# LEDboard.net
KiCad netlist of a schematic drawn in EAGLE
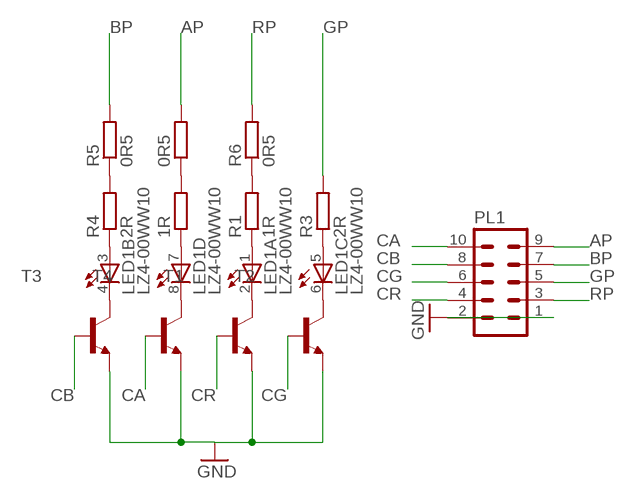
[diagram p0: schematic, sheet 1]

(export (version "E")
  (design (tool "Eeschema 10.0.6"))
  (components
    (comp (ref "0R5")
      (value "R-EU_R0805")
      (footprint "eagle-import:R0805")
      (libsource (lib "eagle-import") (part "R-EU_R0805"))
    )
    (comp (ref "1R")
      (value "R-EU_R1210")
      (footprint "eagle-import:R1210")
      (libsource (lib "eagle-import") (part "R-EU_R1210"))
    )
    (comp (ref "LED1")
      (value "LZ4-00WW10")
      (footprint "eagle-import:LZ4-00WW10")
      (libsource (lib "eagle-import") (part "LZ4-00WW10"))
    )
    (comp (ref "PL1")
      (value "10V")
      (footprint "eagle-import:10V")
      (libsource (lib "eagle-import") (part "10V"))
    )
    (comp (ref "R1")
      (value "1R")
      (footprint "eagle-import:R1210")
      (libsource (lib "eagle-import") (part "R-EU_R1210"))
    )
    (comp (ref "R3")
      (value "2R")
      (footprint "eagle-import:R2512")
      (libsource (lib "eagle-import") (part "R-EU_R2512"))
    )
    (comp (ref "R4")
      (value "2R")
      (footprint "eagle-import:R2512")
      (libsource (lib "eagle-import") (part "R-EU_R2512"))
    )
    (comp (ref "R5")
      (value "0R5")
      (footprint "eagle-import:R0805")
      (libsource (lib "eagle-import") (part "R-EU_R0805"))
    )
    (comp (ref "R6")
      (value "0R5")
      (footprint "eagle-import:R0805")
      (libsource (lib "eagle-import") (part "R-EU_R0805"))
    )
    (comp (ref "T1")
      (value "PZT2222A-NPN-SOT223")
      (footprint "eagle-import:SOT223")
      (libsource (lib "eagle-import") (part "-NPN-SOT223PZT2222A"))
    )
    (comp (ref "T2")
      (value "PZT2222A-NPN-SOT223")
      (footprint "eagle-import:SOT223")
      (libsource (lib "eagle-import") (part "-NPN-SOT223PZT2222A"))
    )
    (comp (ref "T3")
      (value "PZT2222A-NPN-SOT223")
      (footprint "eagle-import:SOT223")
      (libsource (lib "eagle-import") (part "-NPN-SOT223PZT2222A"))
    )
    (comp (ref "T4")
      (value "PZT2222A-NPN-SOT223")
      (footprint "eagle-import:SOT223")
      (libsource (lib "eagle-import") (part "-NPN-SOT223PZT2222A"))
    )
  )
  (nets
    (net (code "1") (name "/AP") (class "Default")
      (node (ref "0R5") (pin "2") (pinfunction "2_2") (pintype "passive"))
      (node (ref "PL1") (pin "9") (pinfunction "9_9") (pintype "passive"))
    )
    (net (code "2") (name "/BP") (class "Default")
      (node (ref "PL1") (pin "7") (pinfunction "7_7") (pintype "passive"))
      (node (ref "R5") (pin "2") (pinfunction "2_2") (pintype "passive"))
    )
    (net (code "3") (name "/CA") (class "Default")
      (node (ref "PL1") (pin "10") (pinfunction "10_10") (pintype "passive"))
      (node (ref "T4") (pin "1") (pinfunction "B_1") (pintype "passive"))
    )
    (net (code "4") (name "/CB") (class "Default")
      (node (ref "PL1") (pin "8") (pinfunction "8_8") (pintype "passive"))
      (node (ref "T3") (pin "1") (pinfunction "B_1") (pintype "passive"))
    )
    (net (code "5") (name "/CG") (class "Default")
      (node (ref "PL1") (pin "6") (pinfunction "6_6") (pintype "passive"))
      (node (ref "T2") (pin "1") (pinfunction "B_1") (pintype "passive"))
    )
    (net (code "6") (name "/CR") (class "Default")
      (node (ref "PL1") (pin "4") (pinfunction "4_4") (pintype "passive"))
      (node (ref "T1") (pin "1") (pinfunction "B_1") (pintype "passive"))
    )
    (net (code "7") (name "/GP") (class "Default")
      (node (ref "PL1") (pin "5") (pinfunction "5_5") (pintype "passive"))
      (node (ref "R3") (pin "2") (pinfunction "2_2") (pintype "passive"))
    )
    (net (code "8") (name "/RP") (class "Default")
      (node (ref "PL1") (pin "3") (pinfunction "3_3") (pintype "passive"))
      (node (ref "R6") (pin "2") (pinfunction "2_2") (pintype "passive"))
    )
    (net (code "9") (name "GND") (class "Default")
      (node (ref "PL1") (pin "1") (pinfunction "1_1") (pintype "passive"))
      (node (ref "PL1") (pin "2") (pinfunction "2_2") (pintype "passive"))
      (node (ref "T1") (pin "3") (pinfunction "E_3") (pintype "passive"))
      (node (ref "T2") (pin "3") (pinfunction "E_3") (pintype "passive"))
      (node (ref "T3") (pin "3") (pinfunction "E_3") (pintype "passive"))
      (node (ref "T4") (pin "3") (pinfunction "E_3") (pintype "passive"))
    )
    (net (code "10") (name "Net-(0R5-Pad1)") (class "Default")
      (node (ref "0R5") (pin "1") (pinfunction "1_1") (pintype "passive"))
      (node (ref "1R") (pin "2") (pinfunction "2_2") (pintype "passive"))
    )
    (net (code "11") (name "Net-(LED1A-A)") (class "Default")
      (node (ref "LED1") (pin "1") (pinfunction "A_1") (pintype "passive"))
      (node (ref "R1") (pin "1") (pinfunction "1_1") (pintype "passive"))
    )
    (net (code "12") (name "Net-(LED1A-C)") (class "Default")
      (node (ref "LED1") (pin "2") (pinfunction "C_2") (pintype "passive"))
      (node (ref "T1") (pin "4") (pinfunction "C_4") (pintype "passive"))
    )
    (net (code "13") (name "Net-(LED1B-A)") (class "Default")
      (node (ref "LED1") (pin "3") (pinfunction "A_3") (pintype "passive"))
      (node (ref "R4") (pin "1") (pinfunction "1_1") (pintype "passive"))
    )
    (net (code "14") (name "Net-(LED1B-C)") (class "Default")
      (node (ref "LED1") (pin "4") (pinfunction "C_4") (pintype "passive"))
      (node (ref "T3") (pin "4") (pinfunction "C_4") (pintype "passive"))
    )
    (net (code "15") (name "Net-(LED1C-A)") (class "Default")
      (node (ref "LED1") (pin "5") (pinfunction "A_5") (pintype "passive"))
      (node (ref "R3") (pin "1") (pinfunction "1_1") (pintype "passive"))
    )
    (net (code "16") (name "Net-(LED1C-C)") (class "Default")
      (node (ref "LED1") (pin "6") (pinfunction "C_6") (pintype "passive"))
      (node (ref "T2") (pin "4") (pinfunction "C_4") (pintype "passive"))
    )
    (net (code "17") (name "Net-(LED1D-A)") (class "Default")
      (node (ref "1R") (pin "1") (pinfunction "1_1") (pintype "passive"))
      (node (ref "LED1") (pin "7") (pinfunction "A_7") (pintype "passive"))
    )
    (net (code "18") (name "Net-(LED1D-C)") (class "Default")
      (node (ref "LED1") (pin "8") (pinfunction "C_8") (pintype "passive"))
      (node (ref "T4") (pin "4") (pinfunction "C_4") (pintype "passive"))
    )
    (net (code "19") (name "Net-(R1-Pad2)") (class "Default")
      (node (ref "R1") (pin "2") (pinfunction "2_2") (pintype "passive"))
      (node (ref "R6") (pin "1") (pinfunction "1_1") (pintype "passive"))
    )
    (net (code "20") (name "Net-(R4-Pad2)") (class "Default")
      (node (ref "R4") (pin "2") (pinfunction "2_2") (pintype "passive"))
      (node (ref "R5") (pin "1") (pinfunction "1_1") (pintype "passive"))
    )
  )
)
